# ADF_1st_mixer_RX.net
KiCad netlist of a schematic drawn in Altium Designer
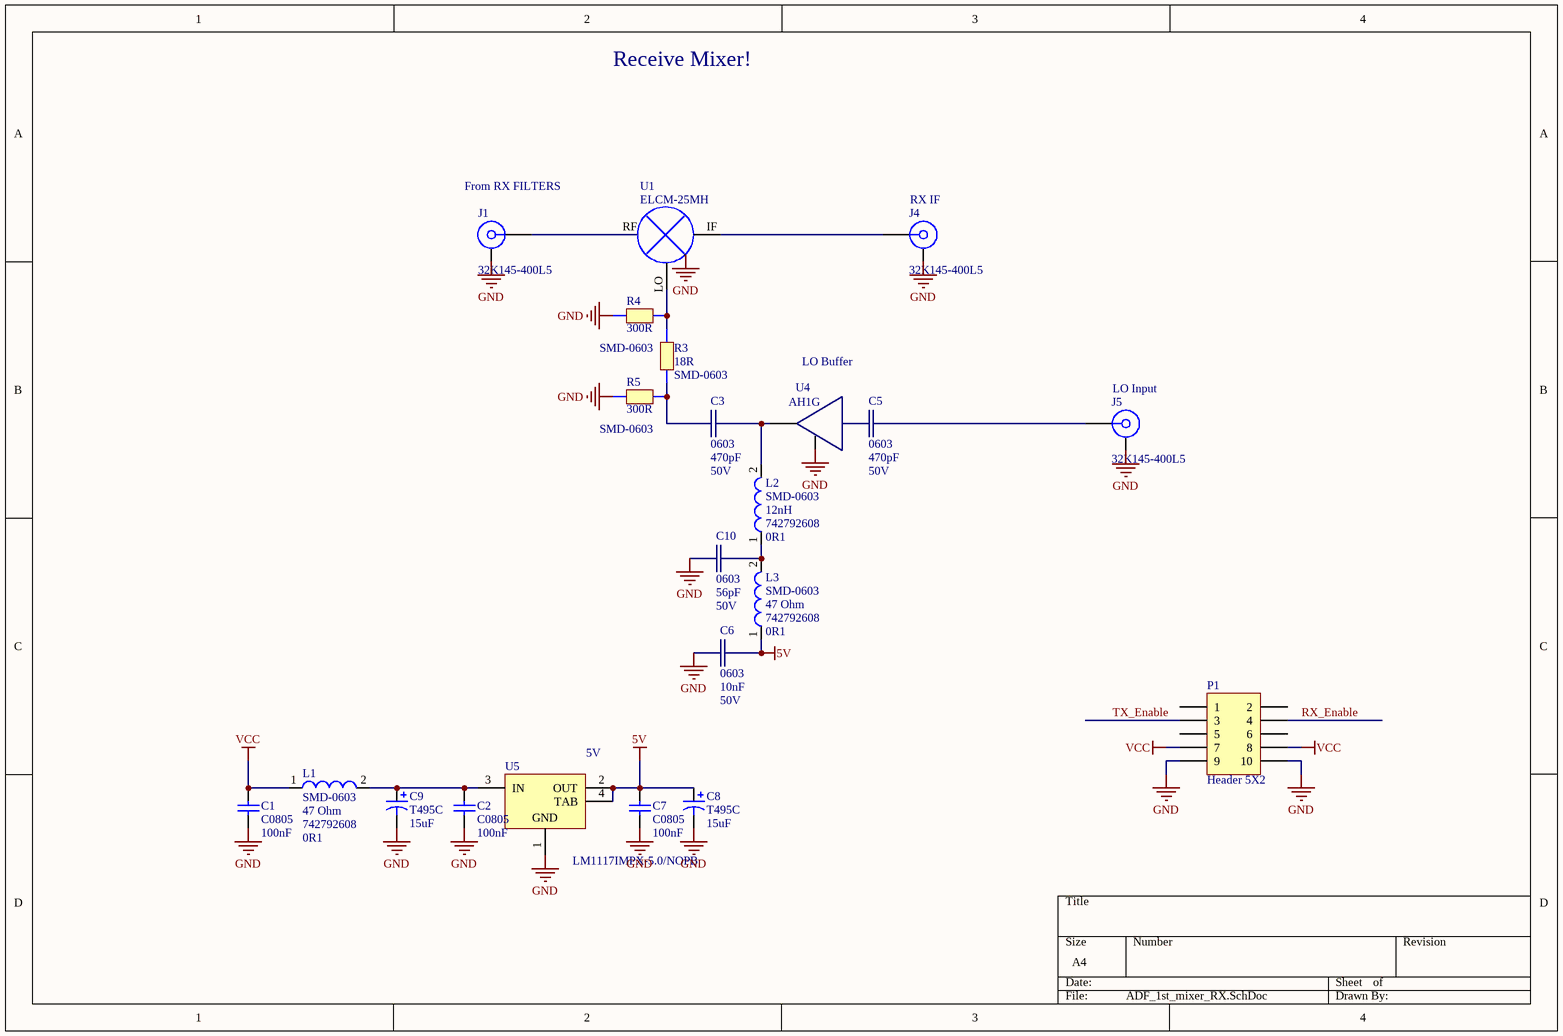
[diagram p0: ADF_1st_mixer_RX.SchDoc]

(export (version "E")
  (design (tool "Eeschema 10.0.6"))
  (components
    (comp (ref "C1")
      (value "C0805")
      (footprint "0805")
      (description "Ceramic Chip Capacitor - Standard")
      (fields (field (name "ALTIUM_VALUE") "100nF") (field (name "PUBLISHER") "Altium Limited"))
      (libsource (lib "KEMET Chip Capacitor") (part "C0805"))
    )
    (comp (ref "C2")
      (value "C0805")
      (footprint "0805")
      (description "Ceramic Chip Capacitor - Standard")
      (fields (field (name "ALTIUM_VALUE") "100nF") (field (name "PUBLISHER") "Altium Limited"))
      (libsource (lib "KEMET Chip Capacitor") (part "C0805"))
    )
    (comp (ref "C3")
      (value "10nF 0603 NP0")
      (footprint "C0603_murata")
      (description "10nF 0603 NP0 muRata")
      (fields
        (field (name "TOLERANCE") "5%")
        (field (name "CASE CODE (IMPERIAL)") "0603")
        (field (name "CAPACITANCE") "470pF")
        (field (name "VOLTAGE") "50V")
      )
      (libsource (lib "ftg_lib") (part "10nF 0603 NP0"))
    )
    (comp (ref "C5")
      (value "10nF 0603 NP0")
      (footprint "C0603_murata")
      (description "10nF 0603 NP0 muRata")
      (fields
        (field (name "TOLERANCE") "5%")
        (field (name "CASE CODE (IMPERIAL)") "0603")
        (field (name "CAPACITANCE") "470pF")
        (field (name "VOLTAGE") "50V")
      )
      (libsource (lib "ftg_lib") (part "10nF 0603 NP0"))
    )
    (comp (ref "C6")
      (value "10nF 0603 NP0")
      (footprint "C0603_murata")
      (description "10nF 0603 NP0 muRata")
      (fields
        (field (name "TOLERANCE") "5%")
        (field (name "CASE CODE (IMPERIAL)") "0603")
        (field (name "CAPACITANCE") "10nF")
        (field (name "VOLTAGE") "50V")
      )
      (libsource (lib "ftg_lib") (part "10nF 0603 NP0"))
    )
    (comp (ref "C7")
      (value "C0805")
      (footprint "0805")
      (description "Ceramic Chip Capacitor - Standard")
      (fields (field (name "ALTIUM_VALUE") "100nF") (field (name "PUBLISHER") "Altium Limited"))
      (libsource (lib "KEMET Chip Capacitor") (part "C0805"))
    )
    (comp (ref "C8")
      (value "T495C")
      (footprint "C")
      (description "Solid Tantalum Chip Capacitor, Standard T495 Series - Low ESR, Surge Robust")
      (fields (field (name "ALTIUM_VALUE") "15uF") (field (name "PUBLISHER") "Altium Limited"))
      (libsource (lib "KEMET Chip Capacitor") (part "T495C"))
    )
    (comp (ref "C9")
      (value "T495C")
      (footprint "C")
      (description "Solid Tantalum Chip Capacitor, Standard T495 Series - Low ESR, Surge Robust")
      (fields (field (name "ALTIUM_VALUE") "15uF") (field (name "PUBLISHER") "Altium Limited"))
      (libsource (lib "KEMET Chip Capacitor") (part "T495C"))
    )
    (comp (ref "C10")
      (value "10nF 0603 NP0")
      (footprint "C0603_murata")
      (description "10nF 0603 NP0 muRata")
      (fields
        (field (name "TOLERANCE") "5%")
        (field (name "CASE CODE (IMPERIAL)") "0603")
        (field (name "CAPACITANCE") "56pF")
        (field (name "VOLTAGE") "50V")
      )
      (libsource (lib "ftg_lib") (part "10nF 0603 NP0"))
    )
    (comp (ref "J1")
      (value "32K145-400L5")
      (footprint "ROS-32K145-400L5_V")
      (description "SMA Right Angle Jack, Edge Mount, Up to 18 GHz, -55 to 155 degC")
      (libsource (lib "Rosenberger SMA") (part "32K145-400L5"))
    )
    (comp (ref "J4")
      (value "32K145-400L5")
      (footprint "ROS-32K145-400L5_V")
      (description "SMA Right Angle Jack, Edge Mount, Up to 18 GHz, -55 to 155 degC")
      (libsource (lib "Rosenberger SMA") (part "32K145-400L5"))
    )
    (comp (ref "J5")
      (value "32K145-400L5")
      (footprint "ROS-32K145-400L5_V")
      (description "SMA Right Angle Jack, Edge Mount, Up to 18 GHz, -55 to 155 degC")
      (libsource (lib "Rosenberger SMA") (part "32K145-400L5"))
    )
    (comp (ref "L1")
      (value "742792608")
      (footprint "SMD-0603")
      (description "SMD EMI Suppression Ferrite Bead WE-CBF, Z = 47 Ohm")
      (fields
        (field (name "PACKAGEREFERENCE") "SMD-0603")
        (field (name "IMPEDANCE") "47 Ohm")
        (field (name "DC_RESISTANCE") "0R1")
      )
      (libsource (lib "AQA_20007_4_Flange") (part "742792608"))
    )
    (comp (ref "L2")
      (value "742792608")
      (footprint "SMD-0603")
      (description "SMD EMI Suppression Ferrite Bead WE-CBF, Z = 47 Ohm")
      (fields
        (field (name "PACKAGEREFERENCE") "SMD-0603")
        (field (name "IMPEDANCE") "12nH")
        (field (name "DC_RESISTANCE") "0R1")
      )
      (libsource (lib "AQA_20007_4_Flange") (part "742792608"))
    )
    (comp (ref "L3")
      (value "742792608")
      (footprint "SMD-0603")
      (description "SMD EMI Suppression Ferrite Bead WE-CBF, Z = 47 Ohm")
      (fields
        (field (name "PACKAGEREFERENCE") "SMD-0603")
        (field (name "IMPEDANCE") "47 Ohm")
        (field (name "DC_RESISTANCE") "0R1")
      )
      (libsource (lib "AQA_20007_4_Flange") (part "742792608"))
    )
    (comp (ref "P1")
      (value "Header 5X2")
      (footprint "HDR2X5")
      (description "Header, 5-Pin, Dual row")
      (fields (field (name "PUBLISHER") "Altium Limited"))
      (libsource (lib "Miscellaneous Connectors") (part "Header 5X2"))
    )
    (comp (ref "R3")
      (value "18R")
      (footprint "RESC1608X06N_0603")
      (description "Bulk SMD Resistor")
      (fields
        (field (name "MANUFACTURER") "PANASONIC")
        (field (name "VOLTAGE") "75V")
        (field (name "PACKAGEREFERENCE") "SMD-0603")
        (field (name "PUBLISHER") "atr")
      )
      (libsource (lib "AQA_atr_2013") (part "Resistor_0R_0603_Bulk"))
    )
    (comp (ref "R4")
      (value "300R")
      (footprint "RESC1608X06N_0603")
      (description "Bulk SMD Resistor")
      (fields
        (field (name "MANUFACTURER") "PANASONIC")
        (field (name "VOLTAGE") "75V")
        (field (name "PACKAGEREFERENCE") "SMD-0603")
        (field (name "PUBLISHER") "atr")
      )
      (libsource (lib "") (part "Resistor_0R_0603_Bulk_1"))
    )
    (comp (ref "R5")
      (value "300R")
      (footprint "RESC1608X06N_0603")
      (description "Bulk SMD Resistor")
      (fields
        (field (name "MANUFACTURER") "PANASONIC")
        (field (name "VOLTAGE") "75V")
        (field (name "PACKAGEREFERENCE") "SMD-0603")
        (field (name "PUBLISHER") "atr")
      )
      (libsource (lib "") (part "Resistor_0R_0603_Bulk_1"))
    )
    (comp (ref "U1") (value "ELCM-25MH") (footprint "SM-87") (libsource (lib "ftg_lib") (part "ELCM-25MH")))
    (comp (ref "U4")
      (value "AH1G")
      (footprint "SOT-89")
      (description "250-4000MHz MMIC")
      (libsource (lib "ftg_lib") (part "AH1G"))
    )
    (comp (ref "U5")
      (value "LM1117IMPX-5.0/NOPB")
      (footprint "MP04A_M")
      (description "800mA Low-Dropout Linear Regulator, 4-pin SOT-223, Pb-Free")
      (fields (field (name "MANUFACTURER") "National Semiconductor"))
      (libsource (lib "Altium Content Vault") (part "PM-REG-LM1086-SOT4"))
    )
  )
  (nets
    (net (code "1") (name "/RX_Enable") (class "Default")
      (node (ref "P1") (pin "4") (pinfunction "4_4") (pintype "passive"))
    )
    (net (code "2") (name "/TX_Enable") (class "Default")
      (node (ref "P1") (pin "3") (pinfunction "3_3") (pintype "passive"))
    )
    (net (code "3") (name "5V") (class "Default")
      (node (ref "C6") (pin "2") (pinfunction "2_2") (pintype "passive"))
      (node (ref "C7") (pin "2") (pinfunction "2_2") (pintype "passive"))
      (node (ref "C8") (pin "1") (pinfunction "1_1") (pintype "passive"))
      (node (ref "L3") (pin "1") (pinfunction "1_1") (pintype "passive"))
      (node (ref "U5") (pin "2") (pinfunction "OUT_2") (pintype "power_in"))
      (node (ref "U5") (pin "4") (pinfunction "TAB_4") (pintype "power_in"))
    )
    (net (code "4") (name "GND") (class "Default")
      (node (ref "C1") (pin "1") (pinfunction "1_1") (pintype "passive"))
      (node (ref "C10") (pin "2") (pinfunction "2_2") (pintype "passive"))
      (node (ref "C2") (pin "1") (pinfunction "1_1") (pintype "passive"))
      (node (ref "C6") (pin "1") (pinfunction "1_1") (pintype "passive"))
      (node (ref "C7") (pin "1") (pinfunction "1_1") (pintype "passive"))
      (node (ref "C8") (pin "2") (pinfunction "2_2") (pintype "passive"))
      (node (ref "C9") (pin "2") (pinfunction "2_2") (pintype "passive"))
      (node (ref "J1") (pin "MP") (pinfunction "MP_MP") (pintype "passive"))
      (node (ref "J4") (pin "MP") (pinfunction "MP_MP") (pintype "passive"))
      (node (ref "J5") (pin "MP") (pinfunction "MP_MP") (pintype "passive"))
      (node (ref "P1") (pin "10") (pinfunction "10_10") (pintype "passive"))
      (node (ref "P1") (pin "9") (pinfunction "9_9") (pintype "passive"))
      (node (ref "R4") (pin "2") (pinfunction "2_2") (pintype "passive"))
      (node (ref "R5") (pin "2") (pinfunction "2_2") (pintype "passive"))
      (node (ref "U1") (pin "GND") (pinfunction "GND_GND") (pintype "passive"))
      (node (ref "U4") (pin "2") (pinfunction "2_2") (pintype "passive"))
      (node (ref "U5") (pin "1") (pinfunction "GND_1") (pintype "power_in"))
    )
    (net (code "5") (name "Net-(C3-Pad1)") (class "Default")
      (node (ref "C3") (pin "1") (pinfunction "1_1") (pintype "passive"))
      (node (ref "R3") (pin "1") (pinfunction "1_1") (pintype "passive"))
      (node (ref "R5") (pin "1") (pinfunction "1_1") (pintype "passive"))
    )
    (net (code "6") (name "Net-(C3-Pad2)") (class "Default")
      (node (ref "C3") (pin "2") (pinfunction "2_2") (pintype "passive"))
      (node (ref "L2") (pin "2") (pinfunction "2_2") (pintype "passive"))
      (node (ref "U4") (pin "3") (pinfunction "3_3") (pintype "passive"))
    )
    (net (code "7") (name "Net-(C5-Pad1)") (class "Default")
      (node (ref "C5") (pin "1") (pinfunction "1_1") (pintype "passive"))
      (node (ref "U4") (pin "1") (pinfunction "1_1") (pintype "passive"))
    )
    (net (code "8") (name "Net-(C5-Pad2)") (class "Default")
      (node (ref "C5") (pin "2") (pinfunction "2_2") (pintype "passive"))
      (node (ref "J5") (pin "1") (pinfunction "1_1") (pintype "passive"))
    )
    (net (code "9") (name "Net-(C10-Pad1)") (class "Default")
      (node (ref "C10") (pin "1") (pinfunction "1_1") (pintype "passive"))
      (node (ref "L2") (pin "1") (pinfunction "1_1") (pintype "passive"))
      (node (ref "L3") (pin "2") (pinfunction "2_2") (pintype "passive"))
    )
    (net (code "10") (name "Net-(J1-Pad1)") (class "Default")
      (node (ref "J1") (pin "1") (pinfunction "1_1") (pintype "passive"))
      (node (ref "U1") (pin "RF") (pinfunction "RF_RF") (pintype "passive"))
    )
    (net (code "11") (name "Net-(J4-Pad1)") (class "Default")
      (node (ref "J4") (pin "1") (pinfunction "1_1") (pintype "passive"))
      (node (ref "U1") (pin "IF") (pinfunction "IF_IF") (pintype "passive"))
    )
    (net (code "12") (name "Net-(R3-Pad2)") (class "Default")
      (node (ref "R3") (pin "2") (pinfunction "2_2") (pintype "passive"))
      (node (ref "R4") (pin "1") (pinfunction "1_1") (pintype "passive"))
      (node (ref "U1") (pin "LO") (pinfunction "LO_LO") (pintype "passive"))
    )
    (net (code "13") (name "Net-(U5-IN)") (class "Default")
      (node (ref "C2") (pin "2") (pinfunction "2_2") (pintype "passive"))
      (node (ref "C9") (pin "1") (pinfunction "1_1") (pintype "passive"))
      (node (ref "L1") (pin "2") (pinfunction "2_2") (pintype "passive"))
      (node (ref "U5") (pin "3") (pinfunction "IN_3") (pintype "power_in"))
    )
    (net (code "14") (name "VCC") (class "Default")
      (node (ref "C1") (pin "2") (pinfunction "2_2") (pintype "passive"))
      (node (ref "L1") (pin "1") (pinfunction "1_1") (pintype "passive"))
      (node (ref "P1") (pin "7") (pinfunction "7_7") (pintype "passive"))
      (node (ref "P1") (pin "8") (pinfunction "8_8") (pintype "passive"))
    )
    (net (code "15") (name "unconnected-(P1-Pad1)") (class "Default")
      (node (ref "P1") (pin "1") (pinfunction "1_1") (pintype "passive"))
    )
    (net (code "16") (name "unconnected-(P1-Pad2)") (class "Default")
      (node (ref "P1") (pin "2") (pinfunction "2_2") (pintype "passive"))
    )
    (net (code "17") (name "unconnected-(P1-Pad5)") (class "Default")
      (node (ref "P1") (pin "5") (pinfunction "5_5") (pintype "passive"))
    )
    (net (code "18") (name "unconnected-(P1-Pad6)") (class "Default")
      (node (ref "P1") (pin "6") (pinfunction "6_6") (pintype "passive"))
    )
  )
)
